# untitled.net
KiCad netlist of a schematic drawn in EAGLE
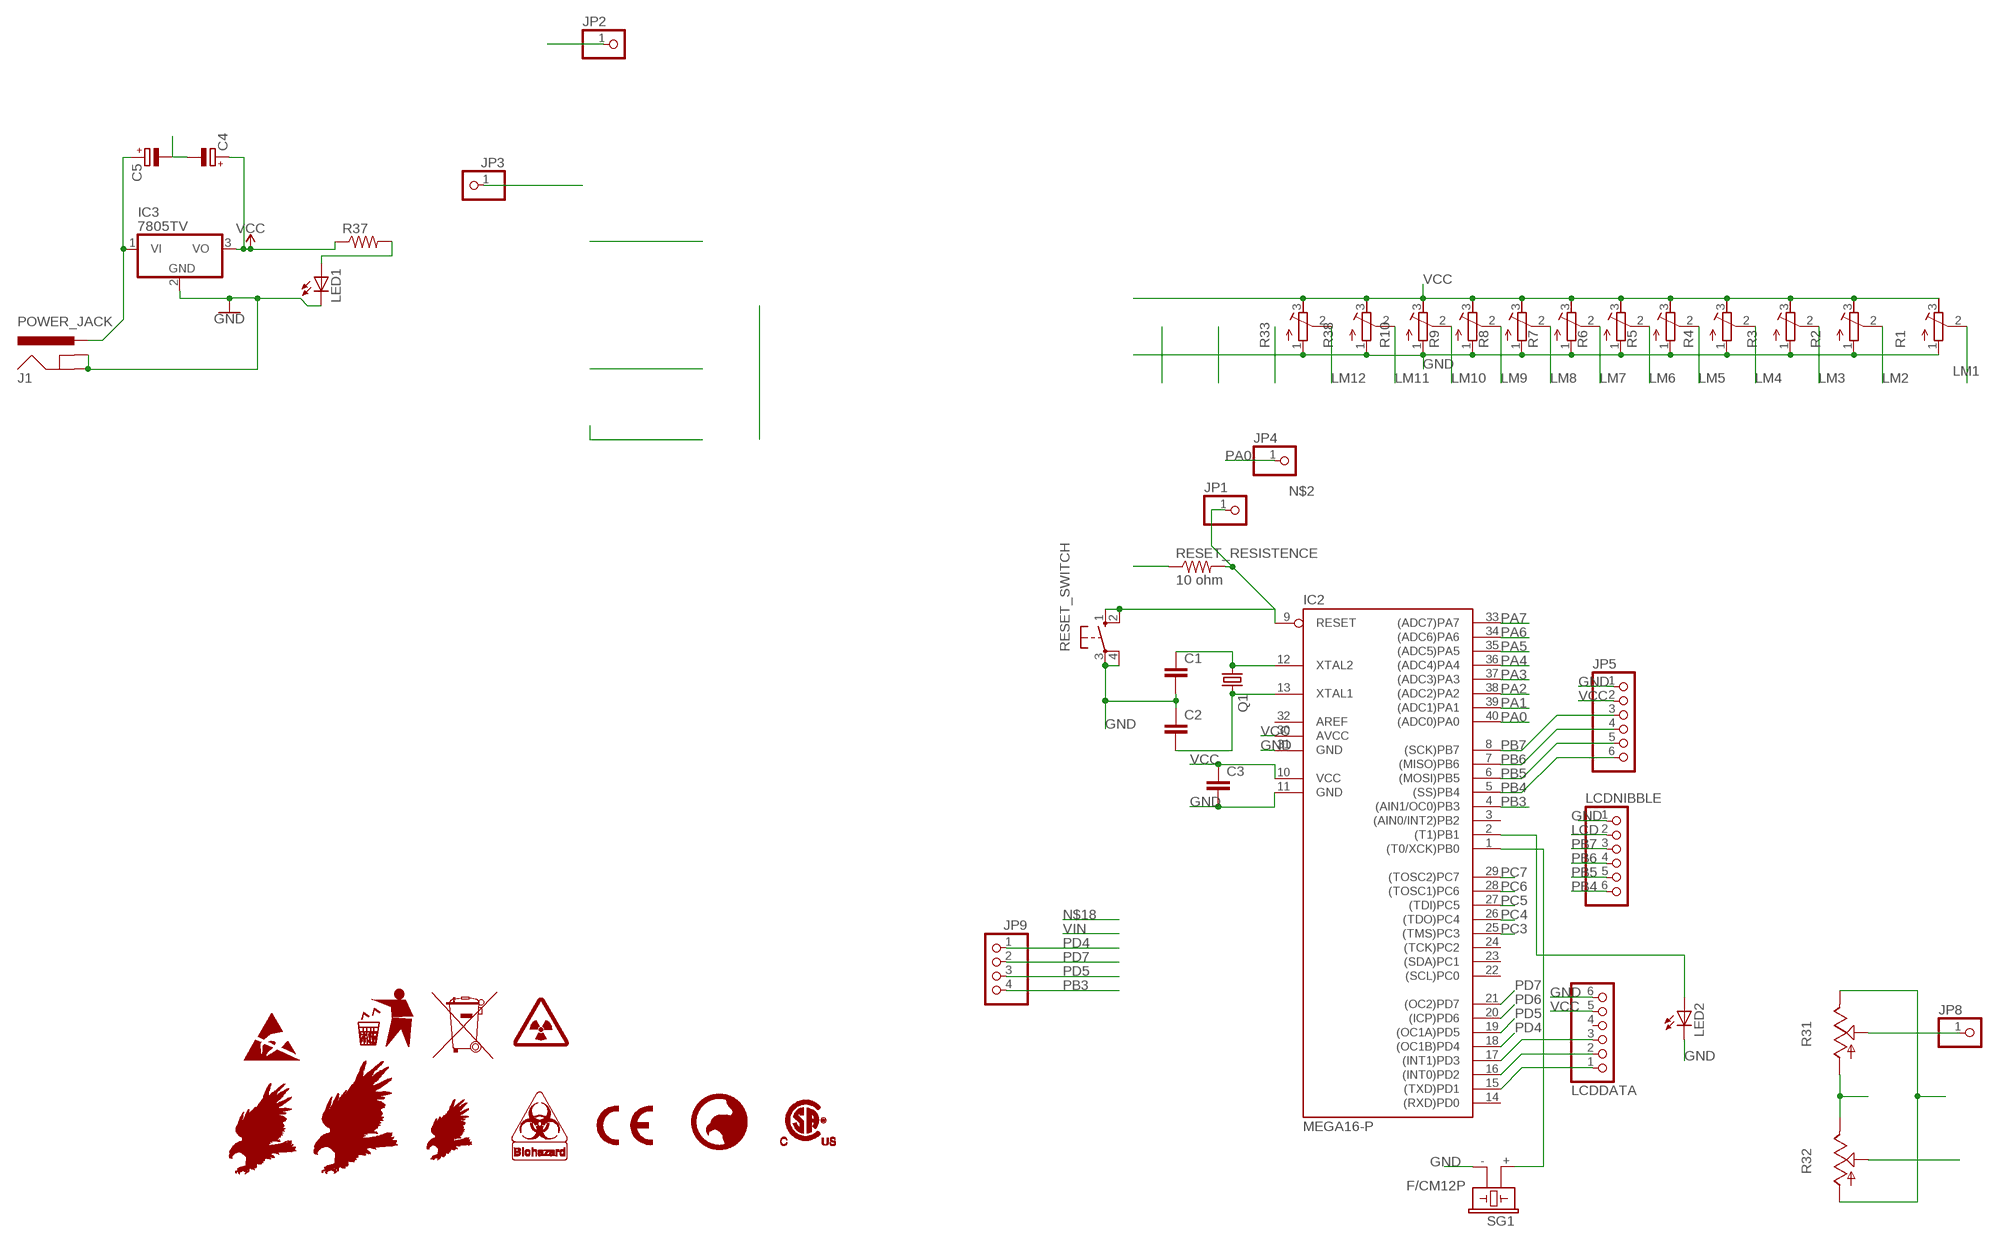
[diagram p0: schematic, sheet 1, part 1 of 2]
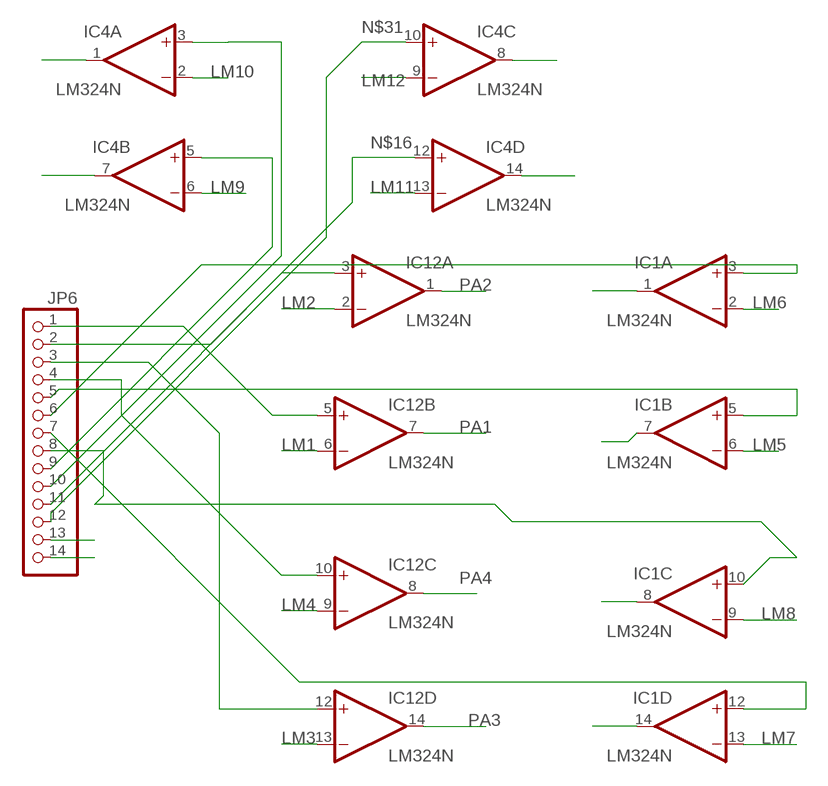
[diagram p1: schematic, sheet 1, part 2 of 2]

(export (version "E")
  (design (tool "Eeschema 10.0.6"))
  (components
    (comp (ref "C1")
      (value "C-EU025-025X050")
      (footprint "eagle-import:C025-025X050")
      (libsource (lib "eagle-import") (part "resistor_C-EU025-025X050"))
    )
    (comp (ref "C2")
      (value "C-EU025-025X050")
      (footprint "eagle-import:C025-025X050")
      (libsource (lib "eagle-import") (part "resistor_C-EU025-025X050"))
    )
    (comp (ref "C3")
      (value "C-EU050-030X075")
      (footprint "eagle-import:C050-030X075")
      (libsource (lib "eagle-import") (part "C-EU050-030X075"))
    )
    (comp (ref "C4")
      (value "CPOL-EUE2.5-6")
      (footprint "eagle-import:E2,5-6")
      (libsource (lib "eagle-import") (part "CPOL-EUE2.5-6"))
    )
    (comp (ref "C5")
      (value "CPOL-EUE2.5-6")
      (footprint "eagle-import:E2,5-6")
      (libsource (lib "eagle-import") (part "CPOL-EUE2.5-6"))
    )
    (comp (ref "IC1")
      (value "LM324N")
      (footprint "eagle-import:DIL14")
      (libsource (lib "eagle-import") (part "LM324N"))
    )
    (comp (ref "IC2")
      (value "MEGA16-P")
      (footprint "eagle-import:DIL40")
      (fields (field (name "MPN") "ATMEGA16-16PU"))
      (libsource (lib "eagle-import") (part "MEGA16-P"))
    )
    (comp (ref "IC3")
      (value "7805TV")
      (footprint "eagle-import:TO220V")
      (libsource (lib "eagle-import") (part "78TV05"))
    )
    (comp (ref "IC4")
      (value "LM324N")
      (footprint "eagle-import:DIL14")
      (libsource (lib "eagle-import") (part "LM324N"))
    )
    (comp (ref "IC12")
      (value "LM324N")
      (footprint "eagle-import:DIL14")
      (libsource (lib "eagle-import") (part "LM324N"))
    )
    (comp (ref "J1")
      (value "POWER_JACK")
      (footprint "eagle-import:POWER_JACK_PTH")
      (libsource (lib "eagle-import") (part "POWER_JACK"))
    )
    (comp (ref "JP1")
      (value "PINHD-1X1")
      (footprint "eagle-import:1X01")
      (libsource (lib "eagle-import") (part "PINHD-1X1"))
    )
    (comp (ref "JP2")
      (value "PINHD-1X1")
      (footprint "eagle-import:1X01")
      (libsource (lib "eagle-import") (part "PINHD-1X1"))
    )
    (comp (ref "JP3")
      (value "PINHD-1X1")
      (footprint "eagle-import:1X01")
      (libsource (lib "eagle-import") (part "PINHD-1X1"))
    )
    (comp (ref "JP4")
      (value "PINHD-1X1")
      (footprint "eagle-import:1X01")
      (libsource (lib "eagle-import") (part "PINHD-1X1"))
    )
    (comp (ref "JP5")
      (value "PINHD-1X6")
      (footprint "eagle-import:1X06")
      (libsource (lib "eagle-import") (part "PINHD-1X6"))
    )
    (comp (ref "JP6")
      (value "PINHD-1X14/90")
      (footprint "eagle-import:1X14_90")
      (libsource (lib "eagle-import") (part "PINHD-1X14/90"))
    )
    (comp (ref "JP8")
      (value "PINHD-1X1")
      (footprint "eagle-import:1X01")
      (libsource (lib "eagle-import") (part "PINHD-1X1"))
    )
    (comp (ref "JP9")
      (value "PINHD-1X4")
      (footprint "eagle-import:1X04")
      (libsource (lib "eagle-import") (part "PINHD-1X4"))
    )
    (comp (ref "LCDDATA")
      (value "PINHD-1X6")
      (footprint "eagle-import:1X06")
      (libsource (lib "eagle-import") (part "PINHD-1X6"))
    )
    (comp (ref "LCDNIBBLE")
      (value "PINHD-1X6")
      (footprint "eagle-import:1X06")
      (libsource (lib "eagle-import") (part "PINHD-1X6"))
    )
    (comp (ref "LED1")
      (value "LED5MM")
      (footprint "eagle-import:LED5MM")
      (libsource (lib "eagle-import") (part "LED5MM"))
    )
    (comp (ref "LED2")
      (value "LED5MM")
      (footprint "eagle-import:LED5MM")
      (libsource (lib "eagle-import") (part "LED5MM"))
    )
    (comp (ref "Q1")
      (value "CRYSTALHC49U70")
      (footprint "eagle-import:HC49U70")
      (libsource (lib "eagle-import") (part "CRYSTALHC49U70"))
    )
    (comp (ref "R1")
      (value "R-TRIMM64W")
      (footprint "eagle-import:RTRIM64W")
      (libsource (lib "eagle-import") (part "R-TRIMM64W"))
    )
    (comp (ref "R2")
      (value "R-TRIMM64W")
      (footprint "eagle-import:RTRIM64W")
      (libsource (lib "eagle-import") (part "R-TRIMM64W"))
    )
    (comp (ref "R3")
      (value "R-TRIMM64W")
      (footprint "eagle-import:RTRIM64W")
      (libsource (lib "eagle-import") (part "R-TRIMM64W"))
    )
    (comp (ref "R4")
      (value "R-TRIMM64W")
      (footprint "eagle-import:RTRIM64W")
      (libsource (lib "eagle-import") (part "R-TRIMM64W"))
    )
    (comp (ref "R5")
      (value "R-TRIMM64W")
      (footprint "eagle-import:RTRIM64W")
      (libsource (lib "eagle-import") (part "R-TRIMM64W"))
    )
    (comp (ref "R6")
      (value "R-TRIMM64W")
      (footprint "eagle-import:RTRIM64W")
      (libsource (lib "eagle-import") (part "R-TRIMM64W"))
    )
    (comp (ref "R7")
      (value "R-TRIMM64W")
      (footprint "eagle-import:RTRIM64W")
      (libsource (lib "eagle-import") (part "R-TRIMM64W"))
    )
    (comp (ref "R8")
      (value "R-TRIMM64W")
      (footprint "eagle-import:RTRIM64W")
      (libsource (lib "eagle-import") (part "R-TRIMM64W"))
    )
    (comp (ref "R9")
      (value "R-TRIMM64W")
      (footprint "eagle-import:RTRIM64W")
      (libsource (lib "eagle-import") (part "R-TRIMM64W"))
    )
    (comp (ref "R10")
      (value "R-TRIMM64W")
      (footprint "eagle-import:RTRIM64W")
      (libsource (lib "eagle-import") (part "R-TRIMM64W"))
    )
    (comp (ref "R31")
      (value "TRIM_US-CA9V")
      (footprint "eagle-import:CA9V")
      (libsource (lib "eagle-import") (part "TRIM_US-CA9V"))
    )
    (comp (ref "R32")
      (value "TRIM_US-CA9V")
      (footprint "eagle-import:CA9V")
      (libsource (lib "eagle-import") (part "TRIM_US-CA9V"))
    )
    (comp (ref "R33")
      (value "R-TRIMM64W")
      (footprint "eagle-import:RTRIM64W")
      (libsource (lib "eagle-import") (part "R-TRIMM64W"))
    )
    (comp (ref "R37")
      (value "R-US_0204/7")
      (footprint "eagle-import:0204_7")
      (libsource (lib "eagle-import") (part "R-US_0204/7"))
    )
    (comp (ref "R38")
      (value "R-TRIMM64W")
      (footprint "eagle-import:RTRIM64W")
      (libsource (lib "eagle-import") (part "R-TRIMM64W"))
    )
    (comp (ref "RESET_RESISTENCE")
      (value "10 ohm")
      (footprint "eagle-import:0204_7")
      (libsource (lib "eagle-import") (part "R-US_0204/7"))
    )
    (comp (ref "RESET_SWITCH")
      (value "10-XX")
      (footprint "eagle-import:B3F-10XX")
      (fields (field (name "MPN") "B3F-1000"))
      (libsource (lib "eagle-import") (part "10-XX"))
    )
    (comp (ref "SG1")
      (value "F/CM12P")
      (footprint "eagle-import:F_CM12P")
      (libsource (lib "eagle-import") (part "F/CM12P"))
    )
  )
  (nets
    (net (code "1") (name "/LCD") (class "Default")
      (node (ref "LCDNIBBLE") (pin "2") (pinfunction "2_2") (pintype "passive"))
      (node (ref "R32") (pin "S") (pinfunction "S_S") (pintype "passive"))
    )
    (net (code "2") (name "/LM1") (class "Default")
      (node (ref "IC12") (pin "6") (pinfunction "-IN_6") (pintype "input"))
      (node (ref "R1") (pin "2") (pinfunction "S_2") (pintype "passive"))
    )
    (net (code "3") (name "/LM2") (class "Default")
      (node (ref "IC12") (pin "2") (pinfunction "-IN_2") (pintype "input"))
      (node (ref "R2") (pin "2") (pinfunction "S_2") (pintype "passive"))
    )
    (net (code "4") (name "/LM3") (class "Default")
      (node (ref "IC12") (pin "13") (pinfunction "-IN_13") (pintype "input"))
      (node (ref "R3") (pin "2") (pinfunction "S_2") (pintype "passive"))
    )
    (net (code "5") (name "/LM4") (class "Default")
      (node (ref "IC12") (pin "9") (pinfunction "-IN_9") (pintype "input"))
      (node (ref "R4") (pin "2") (pinfunction "S_2") (pintype "passive"))
    )
    (net (code "6") (name "/LM5") (class "Default")
      (node (ref "IC1") (pin "6") (pinfunction "-IN_6") (pintype "input"))
      (node (ref "R5") (pin "2") (pinfunction "S_2") (pintype "passive"))
    )
    (net (code "7") (name "/LM6") (class "Default")
      (node (ref "IC1") (pin "2") (pinfunction "-IN_2") (pintype "input"))
      (node (ref "R6") (pin "2") (pinfunction "S_2") (pintype "passive"))
    )
    (net (code "8") (name "/LM7") (class "Default")
      (node (ref "IC1") (pin "13") (pinfunction "-IN_13") (pintype "input"))
      (node (ref "R7") (pin "2") (pinfunction "S_2") (pintype "passive"))
    )
    (net (code "9") (name "/LM8") (class "Default")
      (node (ref "IC1") (pin "9") (pinfunction "-IN_9") (pintype "input"))
      (node (ref "R8") (pin "2") (pinfunction "S_2") (pintype "passive"))
    )
    (net (code "10") (name "/LM9") (class "Default")
      (node (ref "IC4") (pin "6") (pinfunction "-IN_6") (pintype "input"))
      (node (ref "R9") (pin "2") (pinfunction "S_2") (pintype "passive"))
    )
    (net (code "11") (name "/LM10") (class "Default")
      (node (ref "IC4") (pin "2") (pinfunction "-IN_2") (pintype "input"))
      (node (ref "R10") (pin "2") (pinfunction "S_2") (pintype "passive"))
    )
    (net (code "12") (name "/LM11") (class "Default")
      (node (ref "IC4") (pin "13") (pinfunction "-IN_13") (pintype "input"))
      (node (ref "R38") (pin "2") (pinfunction "S_2") (pintype "passive"))
    )
    (net (code "13") (name "/LM12") (class "Default")
      (node (ref "IC4") (pin "9") (pinfunction "-IN_9") (pintype "input"))
      (node (ref "R33") (pin "2") (pinfunction "S_2") (pintype "passive"))
    )
    (net (code "14") (name "/N$2") (class "Default")
      (node (ref "IC2") (pin "9") (pinfunction "RESET_9") (pintype "input"))
      (node (ref "JP1") (pin "1") (pinfunction "1_1") (pintype "passive"))
      (node (ref "RESET_RESISTENCE") (pin "2") (pinfunction "2_2") (pintype "passive"))
      (node (ref "RESET_SWITCH") (pin "1") (pinfunction "S_1") (pintype "passive"))
      (node (ref "RESET_SWITCH") (pin "2") (pinfunction "S1_2") (pintype "passive"))
    )
    (net (code "15") (name "/N$16") (class "Default")
      (node (ref "IC4") (pin "12") (pinfunction "+IN_12") (pintype "input"))
      (node (ref "JP6") (pin "11") (pinfunction "11_11") (pintype "passive"))
    )
    (net (code "17") (name "/N$31") (class "Default")
      (node (ref "IC4") (pin "10") (pinfunction "+IN_10") (pintype "input"))
      (node (ref "JP6") (pin "12") (pinfunction "12_12") (pintype "passive"))
    )
    (net (code "18") (name "/PA0") (class "Default")
      (node (ref "IC2") (pin "40") (pinfunction "(ADC0)PA0_40") (pintype "bidirectional"))
      (node (ref "JP4") (pin "1") (pinfunction "1_1") (pintype "passive"))
    )
    (net (code "19") (name "/PA1") (class "Default")
      (node (ref "IC12") (pin "7") (pinfunction "OUT_7") (pintype "output"))
      (node (ref "IC2") (pin "39") (pinfunction "(ADC1)PA1_39") (pintype "bidirectional"))
    )
    (net (code "20") (name "/PA2") (class "Default")
      (node (ref "IC12") (pin "1") (pinfunction "OUT_1") (pintype "output"))
      (node (ref "IC2") (pin "38") (pinfunction "(ADC2)PA2_38") (pintype "bidirectional"))
    )
    (net (code "21") (name "/PA3") (class "Default")
      (node (ref "IC12") (pin "14") (pinfunction "OUT_14") (pintype "output"))
      (node (ref "IC2") (pin "37") (pinfunction "(ADC3)PA3_37") (pintype "bidirectional"))
    )
    (net (code "22") (name "/PA4") (class "Default")
      (node (ref "IC12") (pin "8") (pinfunction "OUT_8") (pintype "output"))
      (node (ref "IC2") (pin "36") (pinfunction "(ADC4)PA4_36") (pintype "bidirectional"))
    )
    (net (code "23") (name "/PA5") (class "Default")
      (node (ref "IC1") (pin "7") (pinfunction "OUT_7") (pintype "output"))
      (node (ref "IC2") (pin "35") (pinfunction "(ADC5)PA5_35") (pintype "bidirectional"))
    )
    (net (code "24") (name "/PA6") (class "Default")
      (node (ref "IC1") (pin "1") (pinfunction "OUT_1") (pintype "output"))
      (node (ref "IC2") (pin "34") (pinfunction "(ADC6)PA6_34") (pintype "bidirectional"))
    )
    (net (code "25") (name "/PA7") (class "Default")
      (node (ref "IC1") (pin "14") (pinfunction "OUT_14") (pintype "output"))
      (node (ref "IC2") (pin "33") (pinfunction "(ADC7)PA7_33") (pintype "bidirectional"))
    )
    (net (code "26") (name "/PB3") (class "Default")
      (node (ref "IC2") (pin "4") (pinfunction "(AIN1/OC0)PB3_4") (pintype "bidirectional"))
      (node (ref "JP9") (pin "4") (pinfunction "4_4") (pintype "passive"))
    )
    (net (code "27") (name "/PB4") (class "Default")
      (node (ref "IC2") (pin "5") (pinfunction "(SS)PB4_5") (pintype "bidirectional"))
      (node (ref "JP5") (pin "6") (pinfunction "6_6") (pintype "passive"))
      (node (ref "LCDNIBBLE") (pin "6") (pinfunction "6_6") (pintype "passive"))
    )
    (net (code "28") (name "/PB5") (class "Default")
      (node (ref "IC2") (pin "6") (pinfunction "(MOSI)PB5_6") (pintype "bidirectional"))
      (node (ref "JP5") (pin "5") (pinfunction "5_5") (pintype "passive"))
      (node (ref "LCDNIBBLE") (pin "5") (pinfunction "5_5") (pintype "passive"))
    )
    (net (code "29") (name "/PB6") (class "Default")
      (node (ref "IC2") (pin "7") (pinfunction "(MISO)PB6_7") (pintype "bidirectional"))
      (node (ref "JP5") (pin "4") (pinfunction "4_4") (pintype "passive"))
      (node (ref "LCDNIBBLE") (pin "4") (pinfunction "4_4") (pintype "passive"))
    )
    (net (code "30") (name "/PB7") (class "Default")
      (node (ref "IC2") (pin "8") (pinfunction "(SCK)PB7_8") (pintype "bidirectional"))
      (node (ref "JP5") (pin "3") (pinfunction "3_3") (pintype "passive"))
      (node (ref "LCDNIBBLE") (pin "3") (pinfunction "3_3") (pintype "passive"))
    )
    (net (code "31") (name "/PC3") (class "Default")
      (node (ref "IC2") (pin "25") (pinfunction "(TMS)PC3_25") (pintype "bidirectional"))
      (node (ref "IC4") (pin "8") (pinfunction "OUT_8") (pintype "output"))
    )
    (net (code "32") (name "/PC4") (class "Default")
      (node (ref "IC2") (pin "26") (pinfunction "(TDO)PC4_26") (pintype "bidirectional"))
      (node (ref "IC4") (pin "14") (pinfunction "OUT_14") (pintype "output"))
    )
    (net (code "33") (name "/PC5") (class "Default")
      (node (ref "IC2") (pin "27") (pinfunction "(TDI)PC5_27") (pintype "bidirectional"))
      (node (ref "IC4") (pin "1") (pinfunction "OUT_1") (pintype "output"))
    )
    (net (code "34") (name "/PC6") (class "Default")
      (node (ref "IC2") (pin "28") (pinfunction "(TOSC1)PC6_28") (pintype "bidirectional"))
      (node (ref "IC4") (pin "7") (pinfunction "OUT_7") (pintype "output"))
    )
    (net (code "35") (name "/PC7") (class "Default")
      (node (ref "IC1") (pin "8") (pinfunction "OUT_8") (pintype "output"))
      (node (ref "IC2") (pin "29") (pinfunction "(TOSC2)PC7_29") (pintype "bidirectional"))
    )
    (net (code "36") (name "/PD4") (class "Default")
      (node (ref "IC2") (pin "18") (pinfunction "(OC1B)PD4_18") (pintype "bidirectional"))
      (node (ref "JP9") (pin "1") (pinfunction "1_1") (pintype "passive"))
    )
    (net (code "37") (name "/PD5") (class "Default")
      (node (ref "IC2") (pin "19") (pinfunction "(OC1A)PD5_19") (pintype "bidirectional"))
      (node (ref "JP9") (pin "3") (pinfunction "3_3") (pintype "passive"))
    )
    (net (code "38") (name "/PD6") (class "Default")
      (node (ref "IC2") (pin "20") (pinfunction "(ICP)PD6_20") (pintype "bidirectional"))
    )
    (net (code "39") (name "/PD7") (class "Default")
      (node (ref "IC2") (pin "21") (pinfunction "(OC2)PD7_21") (pintype "bidirectional"))
      (node (ref "JP9") (pin "2") (pinfunction "2_2") (pintype "passive"))
    )
    (net (code "41") (name "GND") (class "Default")
      (node (ref "C1") (pin "2") (pinfunction "2_2") (pintype "passive"))
      (node (ref "C2") (pin "1") (pinfunction "1_1") (pintype "passive"))
      (node (ref "C3") (pin "2") (pinfunction "2_2") (pintype "passive"))
      (node (ref "C4") (pin "-") (pinfunction "-_-") (pintype "passive"))
      (node (ref "C5") (pin "-") (pinfunction "-_-") (pintype "passive"))
      (node (ref "IC2") (pin "11") (pinfunction "GND_11") (pintype "power_in"))
      (node (ref "IC2") (pin "31") (pinfunction "GND_31") (pintype "power_in"))
      (node (ref "IC3") (pin "2") (pinfunction "GND_2") (pintype "passive"))
      (node (ref "J1") (pin "GND") (pinfunction "GND_GND") (pintype "bidirectional"))
      (node (ref "J1") (pin "GNDBREAK") (pinfunction "GNDBREAK_GNDBREAK") (pintype "bidirectional"))
      (node (ref "JP2") (pin "1") (pinfunction "1_1") (pintype "passive"))
      (node (ref "JP5") (pin "1") (pinfunction "1_1") (pintype "passive"))
      (node (ref "JP6") (pin "14") (pinfunction "14_14") (pintype "passive"))
      (node (ref "LCDDATA") (pin "6") (pinfunction "6_6") (pintype "passive"))
      (node (ref "LCDNIBBLE") (pin "1") (pinfunction "1_1") (pintype "passive"))
      (node (ref "LED1") (pin "K") (pinfunction "C_K") (pintype "passive"))
      (node (ref "LED2") (pin "K") (pinfunction "C_K") (pintype "passive"))
      (node (ref "R1") (pin "1") (pinfunction "A_1") (pintype "passive"))
      (node (ref "R10") (pin "1") (pinfunction "A_1") (pintype "passive"))
      (node (ref "R2") (pin "1") (pinfunction "A_1") (pintype "passive"))
      (node (ref "R3") (pin "1") (pinfunction "A_1") (pintype "passive"))
      (node (ref "R31") (pin "A") (pinfunction "A_A") (pintype "passive"))
      (node (ref "R32") (pin "E") (pinfunction "E_E") (pintype "passive"))
      (node (ref "R33") (pin "1") (pinfunction "A_1") (pintype "passive"))
      (node (ref "R38") (pin "1") (pinfunction "A_1") (pintype "passive"))
      (node (ref "R4") (pin "1") (pinfunction "A_1") (pintype "passive"))
      (node (ref "R5") (pin "1") (pinfunction "A_1") (pintype "passive"))
      (node (ref "R6") (pin "1") (pinfunction "A_1") (pintype "passive"))
      (node (ref "R7") (pin "1") (pinfunction "A_1") (pintype "passive"))
      (node (ref "R8") (pin "1") (pinfunction "A_1") (pintype "passive"))
      (node (ref "R9") (pin "1") (pinfunction "A_1") (pintype "passive"))
      (node (ref "RESET_SWITCH") (pin "3") (pinfunction "P_3") (pintype "passive"))
      (node (ref "RESET_SWITCH") (pin "4") (pinfunction "P1_4") (pintype "passive"))
      (node (ref "SG1") (pin "-") (pinfunction "2_-") (pintype "passive"))
    )
    (net (code "42") (name "Net-(IC1A-+IN)") (class "Default")
      (node (ref "IC1") (pin "3") (pinfunction "+IN_3") (pintype "input"))
      (node (ref "JP6") (pin "6") (pinfunction "6_6") (pintype "passive"))
    )
    (net (code "43") (name "Net-(IC1B-+IN)") (class "Default")
      (node (ref "IC1") (pin "5") (pinfunction "+IN_5") (pintype "input"))
      (node (ref "JP6") (pin "5") (pinfunction "5_5") (pintype "passive"))
    )
    (net (code "44") (name "Net-(IC1C-+IN)") (class "Default")
      (node (ref "IC1") (pin "10") (pinfunction "+IN_10") (pintype "input"))
      (node (ref "JP6") (pin "8") (pinfunction "8_8") (pintype "passive"))
    )
    (net (code "45") (name "Net-(IC1D-+IN)") (class "Default")
      (node (ref "IC1") (pin "12") (pinfunction "+IN_12") (pintype "input"))
      (node (ref "JP6") (pin "7") (pinfunction "7_7") (pintype "passive"))
    )
    (net (code "46") (name "Net-(IC2-(INT0)PD2)") (class "Default")
      (node (ref "IC2") (pin "16") (pinfunction "(INT0)PD2_16") (pintype "bidirectional"))
      (node (ref "LCDDATA") (pin "2") (pinfunction "2_2") (pintype "passive"))
    )
    (net (code "47") (name "Net-(IC2-(INT1)PD3)") (class "Default")
      (node (ref "IC2") (pin "17") (pinfunction "(INT1)PD3_17") (pintype "bidirectional"))
      (node (ref "LCDDATA") (pin "3") (pinfunction "3_3") (pintype "passive"))
    )
    (net (code "48") (name "Net-(IC2-(T0{slash}XCK)PB0)") (class "Default")
      (node (ref "IC2") (pin "1") (pinfunction "(T0/XCK)PB0_1") (pintype "bidirectional"))
      (node (ref "SG1") (pin "+") (pinfunction "1_+") (pintype "passive"))
    )
    (net (code "49") (name "Net-(IC2-(T1)PB1)") (class "Default")
      (node (ref "IC2") (pin "2") (pinfunction "(T1)PB1_2") (pintype "bidirectional"))
      (node (ref "LED2") (pin "A") (pinfunction "A_A") (pintype "passive"))
    )
    (net (code "50") (name "Net-(IC2-(TXD)PD1)") (class "Default")
      (node (ref "IC2") (pin "15") (pinfunction "(TXD)PD1_15") (pintype "bidirectional"))
      (node (ref "LCDDATA") (pin "1") (pinfunction "1_1") (pintype "passive"))
    )
    (net (code "51") (name "Net-(IC2-XTAL1)") (class "Default")
      (node (ref "C2") (pin "2") (pinfunction "2_2") (pintype "passive"))
      (node (ref "IC2") (pin "13") (pinfunction "XTAL1_13") (pintype "bidirectional"))
      (node (ref "Q1") (pin "2") (pinfunction "2_2") (pintype "passive"))
    )
    (net (code "52") (name "Net-(IC2-XTAL2)") (class "Default")
      (node (ref "C1") (pin "1") (pinfunction "1_1") (pintype "passive"))
      (node (ref "IC2") (pin "12") (pinfunction "XTAL2_12") (pintype "bidirectional"))
      (node (ref "Q1") (pin "1") (pinfunction "1_1") (pintype "passive"))
    )
    (net (code "53") (name "Net-(IC3-VI)") (class "Default")
      (node (ref "C5") (pin "+") (pinfunction "+_+") (pintype "passive"))
      (node (ref "IC3") (pin "1") (pinfunction "VI_1") (pintype "input"))
      (node (ref "J1") (pin "PWR") (pinfunction "PWR_PWR") (pintype "bidirectional"))
    )
    (net (code "54") (name "Net-(IC4A-+IN)") (class "Default")
      (node (ref "IC4") (pin "3") (pinfunction "+IN_3") (pintype "input"))
      (node (ref "JP6") (pin "10") (pinfunction "10_10") (pintype "passive"))
    )
    (net (code "55") (name "Net-(IC4B-+IN)") (class "Default")
      (node (ref "IC4") (pin "5") (pinfunction "+IN_5") (pintype "input"))
      (node (ref "JP6") (pin "9") (pinfunction "9_9") (pintype "passive"))
    )
    (net (code "56") (name "Net-(IC12A-+IN)") (class "Default")
      (node (ref "IC12") (pin "3") (pinfunction "+IN_3") (pintype "input"))
      (node (ref "JP6") (pin "2") (pinfunction "2_2") (pintype "passive"))
    )
    (net (code "57") (name "Net-(IC12B-+IN)") (class "Default")
      (node (ref "IC12") (pin "5") (pinfunction "+IN_5") (pintype "input"))
      (node (ref "JP6") (pin "1") (pinfunction "1_1") (pintype "passive"))
    )
    (net (code "58") (name "Net-(IC12C-+IN)") (class "Default")
      (node (ref "IC12") (pin "10") (pinfunction "+IN_10") (pintype "input"))
      (node (ref "JP6") (pin "4") (pinfunction "4_4") (pintype "passive"))
    )
    (net (code "59") (name "Net-(IC12D-+IN)") (class "Default")
      (node (ref "IC12") (pin "12") (pinfunction "+IN_12") (pintype "input"))
      (node (ref "JP6") (pin "3") (pinfunction "3_3") (pintype "passive"))
    )
    (net (code "60") (name "Net-(JP8-Pad1)") (class "Default")
      (node (ref "JP8") (pin "1") (pinfunction "1_1") (pintype "passive"))
      (node (ref "R31") (pin "S") (pinfunction "S_S") (pintype "passive"))
    )
    (net (code "61") (name "Net-(LED1-PadA)") (class "Default")
      (node (ref "LED1") (pin "A") (pinfunction "A_A") (pintype "passive"))
      (node (ref "R37") (pin "2") (pinfunction "2_2") (pintype "passive"))
    )
    (net (code "62") (name "VCC") (class "Default")
      (node (ref "C3") (pin "1") (pinfunction "1_1") (pintype "passive"))
      (node (ref "C4") (pin "+") (pinfunction "+_+") (pintype "passive"))
      (node (ref "IC2") (pin "10") (pinfunction "VCC_10") (pintype "power_in"))
      (node (ref "IC2") (pin "30") (pinfunction "AVCC_30") (pintype "power_in"))
      (node (ref "IC3") (pin "3") (pinfunction "VO_3") (pintype "passive"))
      (node (ref "JP3") (pin "1") (pinfunction "1_1") (pintype "passive"))
      (node (ref "JP5") (pin "2") (pinfunction "2_2") (pintype "passive"))
      (node (ref "JP6") (pin "13") (pinfunction "13_13") (pintype "passive"))
      (node (ref "LCDDATA") (pin "5") (pinfunction "5_5") (pintype "passive"))
      (node (ref "R1") (pin "3") (pinfunction "E_3") (pintype "passive"))
      (node (ref "R10") (pin "3") (pinfunction "E_3") (pintype "passive"))
      (node (ref "R2") (pin "3") (pinfunction "E_3") (pintype "passive"))
      (node (ref "R3") (pin "3") (pinfunction "E_3") (pintype "passive"))
      (node (ref "R31") (pin "E") (pinfunction "E_E") (pintype "passive"))
      (node (ref "R32") (pin "A") (pinfunction "A_A") (pintype "passive"))
      (node (ref "R33") (pin "3") (pinfunction "E_3") (pintype "passive"))
      (node (ref "R37") (pin "1") (pinfunction "1_1") (pintype "passive"))
      (node (ref "R38") (pin "3") (pinfunction "E_3") (pintype "passive"))
      (node (ref "R4") (pin "3") (pinfunction "E_3") (pintype "passive"))
      (node (ref "R5") (pin "3") (pinfunction "E_3") (pintype "passive"))
      (node (ref "R6") (pin "3") (pinfunction "E_3") (pintype "passive"))
      (node (ref "R7") (pin "3") (pinfunction "E_3") (pintype "passive"))
      (node (ref "R8") (pin "3") (pinfunction "E_3") (pintype "passive"))
      (node (ref "R9") (pin "3") (pinfunction "E_3") (pintype "passive"))
      (node (ref "RESET_RESISTENCE") (pin "1") (pinfunction "1_1") (pintype "passive"))
    )
    (net (code "63") (name "unconnected-(IC2-(AIN0{slash}INT2)PB2-Pad3)") (class "Default")
      (node (ref "IC2") (pin "3") (pinfunction "(AIN0/INT2)PB2_3") (pintype "bidirectional"))
    )
    (net (code "64") (name "unconnected-(IC2-(RXD)PD0-Pad14)") (class "Default")
      (node (ref "IC2") (pin "14") (pinfunction "(RXD)PD0_14") (pintype "bidirectional"))
    )
    (net (code "65") (name "unconnected-(IC2-(SCL)PC0-Pad22)") (class "Default")
      (node (ref "IC2") (pin "22") (pinfunction "(SCL)PC0_22") (pintype "bidirectional"))
    )
    (net (code "66") (name "unconnected-(IC2-(SDA)PC1-Pad23)") (class "Default")
      (node (ref "IC2") (pin "23") (pinfunction "(SDA)PC1_23") (pintype "bidirectional"))
    )
    (net (code "67") (name "unconnected-(IC2-(TCK)PC2-Pad24)") (class "Default")
      (node (ref "IC2") (pin "24") (pinfunction "(TCK)PC2_24") (pintype "bidirectional"))
    )
    (net (code "68") (name "unconnected-(IC2-AREF-Pad32)") (class "Default")
      (node (ref "IC2") (pin "32") (pinfunction "AREF_32") (pintype "passive"))
    )
    (net (code "69") (name "unconnected-(LCDDATA-Pad4)") (class "Default")
      (node (ref "LCDDATA") (pin "4") (pinfunction "4_4") (pintype "passive"))
    )
  )
)
